# MJU.net
KiCad netlist of a schematic drawn in EAGLE
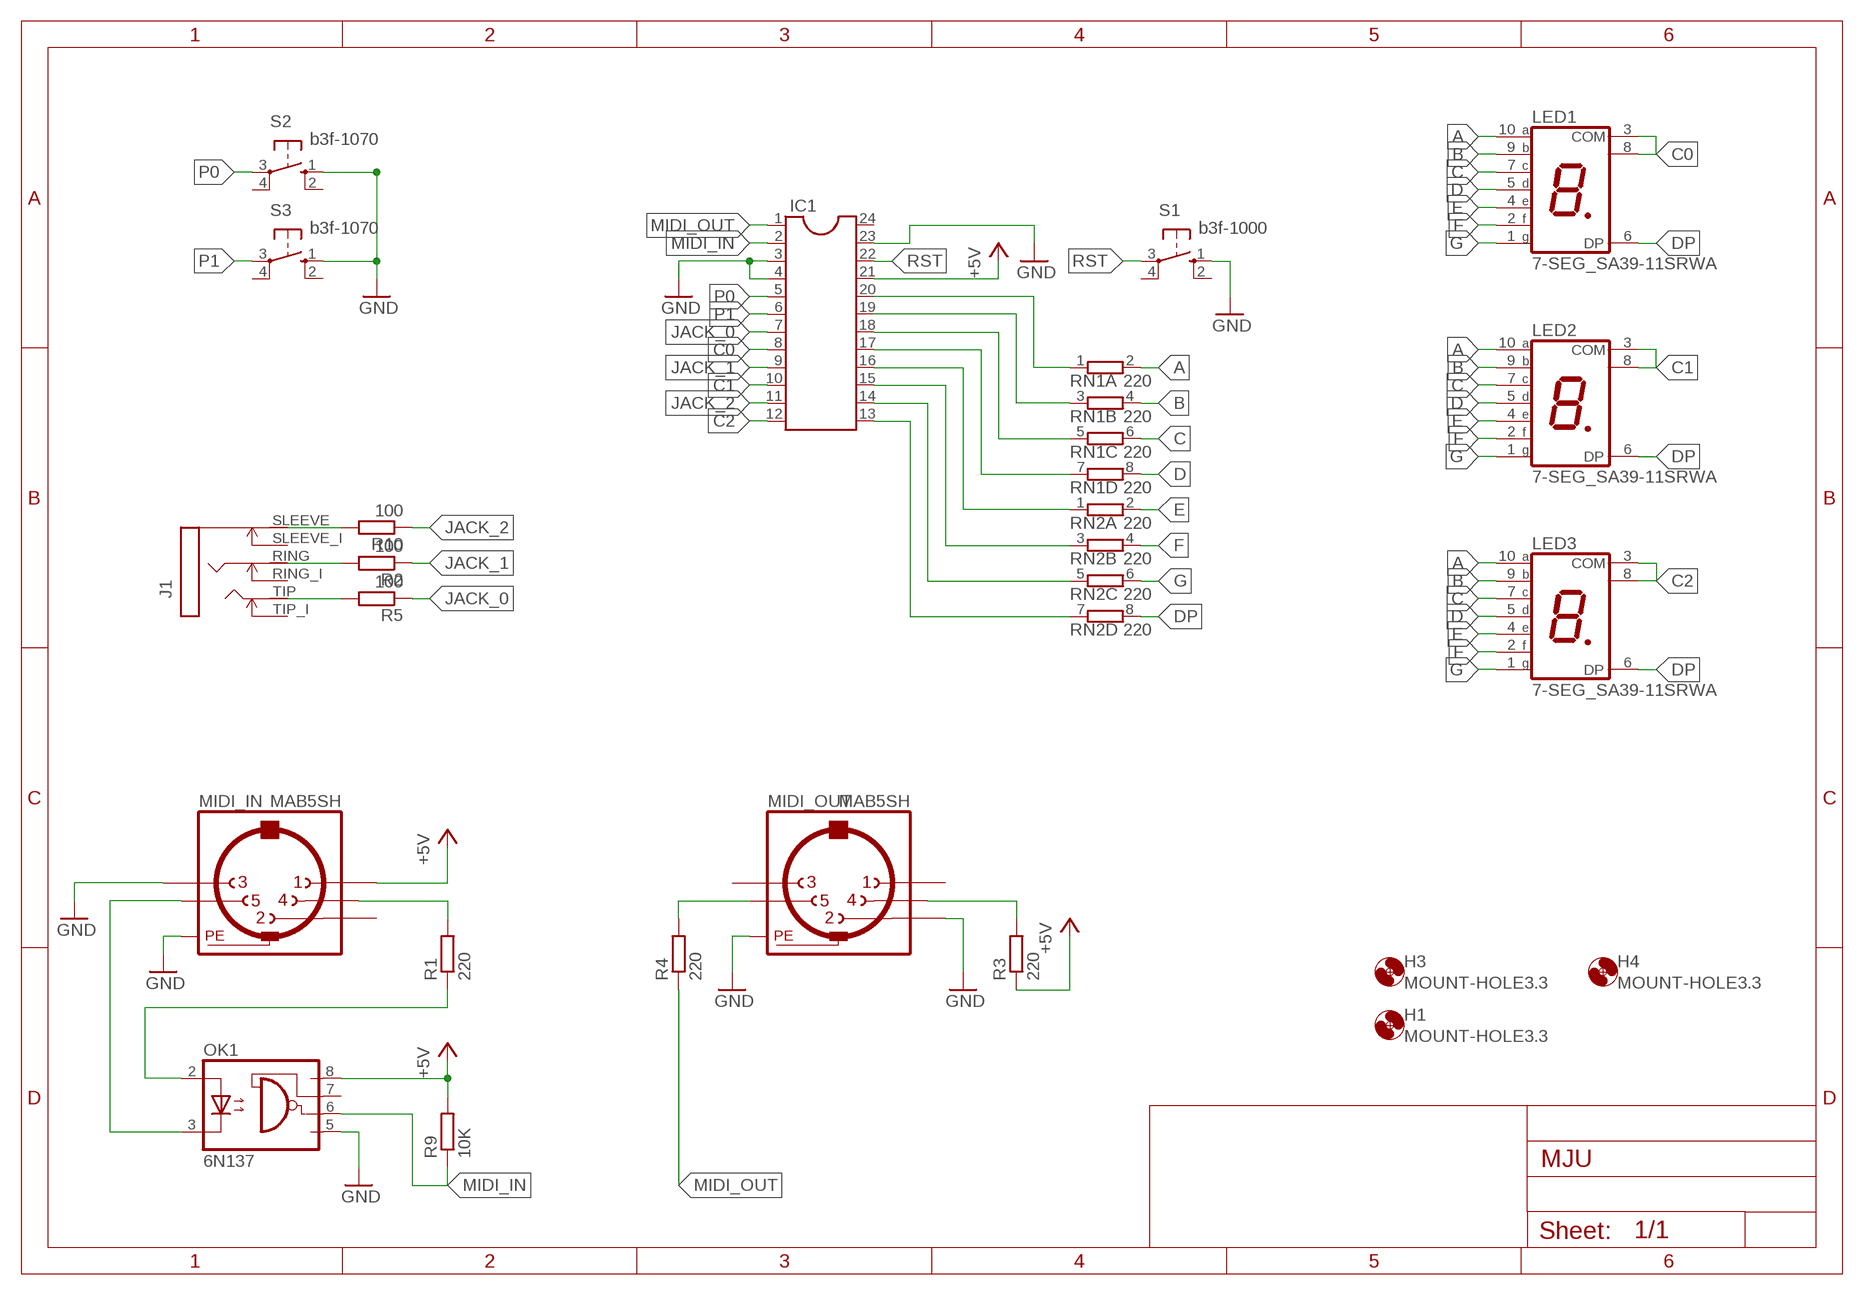
[diagram p0: schematic, sheet 1]

(export (version "E")
  (design (tool "Eeschema 10.0.6"))
  (components
    (comp (ref "H1")
      (value "MOUNT-HOLE3.3")
      (footprint "eagle-import:3,3")
      (libsource (lib "eagle-import") (part "MOUNT-HOLE3.3"))
    )
    (comp (ref "H3")
      (value "MOUNT-HOLE3.3")
      (footprint "eagle-import:3,3")
      (libsource (lib "eagle-import") (part "MOUNT-HOLE3.3"))
    )
    (comp (ref "H4")
      (value "MOUNT-HOLE3.3")
      (footprint "eagle-import:3,3")
      (libsource (lib "eagle-import") (part "MOUNT-HOLE3.3"))
    )
    (comp (ref "IC1")
      (value "DIL24-6")
      (footprint "eagle-import:DIL24-6")
      (libsource (lib "eagle-import") (part "DIL24-6"))
    )
    (comp (ref "J1")
      (value "STEREOSWJACK_ST_TRS_INT")
      (footprint "eagle-import:ST_JACK_TRS_INT")
      (libsource (lib "eagle-import") (part "STEREOSWJACK_ST_TRS_INT"))
    )
    (comp (ref "LED1")
      (value "7-SEG_SA39-11SRWA")
      (footprint "eagle-import:SA39-11SRWA")
      (libsource (lib "eagle-import") (part "7-SEG_SA39-11SRWA"))
    )
    (comp (ref "LED2")
      (value "7-SEG_SA39-11SRWA")
      (footprint "eagle-import:SA39-11SRWA")
      (libsource (lib "eagle-import") (part "7-SEG_SA39-11SRWA"))
    )
    (comp (ref "LED3")
      (value "7-SEG_SA39-11SRWA")
      (footprint "eagle-import:SA39-11SRWA")
      (libsource (lib "eagle-import") (part "7-SEG_SA39-11SRWA"))
    )
    (comp (ref "MIDI_IN")
      (value "MAB5SH")
      (footprint "eagle-import:MAB5SH")
      (libsource (lib "eagle-import") (part "MAB5SH"))
    )
    (comp (ref "MIDI_OUT")
      (value "MAB5SH")
      (footprint "eagle-import:MAB5SH")
      (libsource (lib "eagle-import") (part "MAB5SH"))
    )
    (comp (ref "OK1")
      (value "6N137")
      (footprint "eagle-import:DIL08")
      (libsource (lib "eagle-import") (part "6N137"))
    )
    (comp (ref "R1")
      (value "220")
      (footprint "eagle-import:0207_7")
      (libsource (lib "eagle-import") (part "R-EU_0207/7"))
    )
    (comp (ref "R2")
      (value "100")
      (footprint "eagle-import:0207_7")
      (libsource (lib "eagle-import") (part "R-EU_0207/7"))
    )
    (comp (ref "R3")
      (value "220")
      (footprint "eagle-import:0207_7")
      (libsource (lib "eagle-import") (part "R-EU_0207/7"))
    )
    (comp (ref "R4")
      (value "220")
      (footprint "eagle-import:0207_7")
      (libsource (lib "eagle-import") (part "R-EU_0207/7"))
    )
    (comp (ref "R5")
      (value "100")
      (footprint "eagle-import:0207_7")
      (libsource (lib "eagle-import") (part "R-EU_0207/7"))
    )
    (comp (ref "R9")
      (value "10K")
      (footprint "eagle-import:0207_7")
      (libsource (lib "eagle-import") (part "R-EU_0207/7"))
    )
    (comp (ref "R10")
      (value "100")
      (footprint "eagle-import:0207_7")
      (libsource (lib "eagle-import") (part "R-EU_0207/7"))
    )
    (comp (ref "RN1")
      (value "220")
      (footprint "eagle-import:SIL8")
      (libsource (lib "eagle-import") (part "E4R"))
    )
    (comp (ref "RN2")
      (value "220")
      (footprint "eagle-import:SIL8")
      (libsource (lib "eagle-import") (part "E4R"))
    )
    (comp (ref "S1")
      (value "b3f-1000")
      (footprint "eagle-import:B3F-10XX")
      (fields (field (name "MPN") "B3F-1000"))
      (libsource (lib "eagle-import") (part "10-XX"))
    )
    (comp (ref "S2")
      (value "b3f-1070")
      (footprint "eagle-import:B3F-10XX")
      (fields (field (name "MPN") "B3F-1000"))
      (libsource (lib "eagle-import") (part "10-XX"))
    )
    (comp (ref "S3")
      (value "b3f-1070")
      (footprint "eagle-import:B3F-10XX")
      (fields (field (name "MPN") "B3F-1000"))
      (libsource (lib "eagle-import") (part "10-XX"))
    )
  )
  (nets
    (net (code "1") (name "+5V") (class "Default")
      (node (ref "IC1") (pin "21") (pinfunction "21_21") (pintype "passive"))
      (node (ref "MIDI_IN") (pin "1") (pinfunction "1_1") (pintype "passive"))
      (node (ref "OK1") (pin "8") (pinfunction "VCC_8") (pintype "passive"))
      (node (ref "R3") (pin "1") (pinfunction "1_1") (pintype "passive"))
      (node (ref "R9") (pin "2") (pinfunction "2_2") (pintype "passive"))
    )
    (net (code "2") (name "A") (class "Default")
      (node (ref "LED1") (pin "10") (pinfunction "A_10") (pintype "passive"))
      (node (ref "LED2") (pin "10") (pinfunction "A_10") (pintype "passive"))
      (node (ref "LED3") (pin "10") (pinfunction "A_10") (pintype "passive"))
      (node (ref "RN1") (pin "2") (pinfunction "2_2") (pintype "passive"))
    )
    (net (code "3") (name "B") (class "Default")
      (node (ref "LED1") (pin "9") (pinfunction "B_9") (pintype "passive"))
      (node (ref "LED2") (pin "9") (pinfunction "B_9") (pintype "passive"))
      (node (ref "LED3") (pin "9") (pinfunction "B_9") (pintype "passive"))
      (node (ref "RN1") (pin "4") (pinfunction "2_4") (pintype "passive"))
    )
    (net (code "4") (name "C") (class "Default")
      (node (ref "LED1") (pin "7") (pinfunction "C_7") (pintype "passive"))
      (node (ref "LED2") (pin "7") (pinfunction "C_7") (pintype "passive"))
      (node (ref "LED3") (pin "7") (pinfunction "C_7") (pintype "passive"))
      (node (ref "RN1") (pin "6") (pinfunction "2_6") (pintype "passive"))
    )
    (net (code "5") (name "C0") (class "Default")
      (node (ref "IC1") (pin "8") (pinfunction "8_8") (pintype "passive"))
      (node (ref "LED1") (pin "3") (pinfunction "COM_3") (pintype "passive"))
      (node (ref "LED1") (pin "8") (pinfunction "COM_8") (pintype "passive"))
    )
    (net (code "6") (name "C1") (class "Default")
      (node (ref "IC1") (pin "10") (pinfunction "10_10") (pintype "passive"))
      (node (ref "LED2") (pin "3") (pinfunction "COM_3") (pintype "passive"))
      (node (ref "LED2") (pin "8") (pinfunction "COM_8") (pintype "passive"))
    )
    (net (code "7") (name "C2") (class "Default")
      (node (ref "IC1") (pin "12") (pinfunction "12_12") (pintype "passive"))
      (node (ref "LED3") (pin "3") (pinfunction "COM_3") (pintype "passive"))
      (node (ref "LED3") (pin "8") (pinfunction "COM_8") (pintype "passive"))
    )
    (net (code "8") (name "D") (class "Default")
      (node (ref "LED1") (pin "5") (pinfunction "D_5") (pintype "passive"))
      (node (ref "LED2") (pin "5") (pinfunction "D_5") (pintype "passive"))
      (node (ref "LED3") (pin "5") (pinfunction "D_5") (pintype "passive"))
      (node (ref "RN1") (pin "8") (pinfunction "2_8") (pintype "passive"))
    )
    (net (code "9") (name "DP") (class "Default")
      (node (ref "LED1") (pin "6") (pinfunction "DP_6") (pintype "passive"))
      (node (ref "LED2") (pin "6") (pinfunction "DP_6") (pintype "passive"))
      (node (ref "LED3") (pin "6") (pinfunction "DP_6") (pintype "passive"))
      (node (ref "RN2") (pin "8") (pinfunction "2_8") (pintype "passive"))
    )
    (net (code "10") (name "E") (class "Default")
      (node (ref "LED1") (pin "4") (pinfunction "E_4") (pintype "passive"))
      (node (ref "LED2") (pin "4") (pinfunction "E_4") (pintype "passive"))
      (node (ref "LED3") (pin "4") (pinfunction "E_4") (pintype "passive"))
      (node (ref "RN2") (pin "2") (pinfunction "2_2") (pintype "passive"))
    )
    (net (code "11") (name "F") (class "Default")
      (node (ref "LED1") (pin "2") (pinfunction "F_2") (pintype "passive"))
      (node (ref "LED2") (pin "2") (pinfunction "F_2") (pintype "passive"))
      (node (ref "LED3") (pin "2") (pinfunction "F_2") (pintype "passive"))
      (node (ref "RN2") (pin "4") (pinfunction "2_4") (pintype "passive"))
    )
    (net (code "12") (name "G") (class "Default")
      (node (ref "LED1") (pin "1") (pinfunction "G_1") (pintype "passive"))
      (node (ref "LED2") (pin "1") (pinfunction "G_1") (pintype "passive"))
      (node (ref "LED3") (pin "1") (pinfunction "G_1") (pintype "passive"))
      (node (ref "RN2") (pin "6") (pinfunction "2_6") (pintype "passive"))
    )
    (net (code "13") (name "GND") (class "Default")
      (node (ref "IC1") (pin "23") (pinfunction "23_23") (pintype "passive"))
      (node (ref "IC1") (pin "3") (pinfunction "3_3") (pintype "passive"))
      (node (ref "IC1") (pin "4") (pinfunction "4_4") (pintype "passive"))
      (node (ref "MIDI_IN") (pin "3") (pinfunction "3_3") (pintype "passive"))
      (node (ref "MIDI_IN") (pin "PE") (pinfunction "PE_PE") (pintype "power_in"))
      (node (ref "MIDI_IN") (pin "PE@") (pinfunction "PE_PE@") (pintype "power_in"))
      (node (ref "MIDI_OUT") (pin "2") (pinfunction "2_2") (pintype "passive"))
      (node (ref "MIDI_OUT") (pin "PE") (pinfunction "PE_PE") (pintype "power_in"))
      (node (ref "MIDI_OUT") (pin "PE@") (pinfunction "PE_PE@") (pintype "power_in"))
      (node (ref "OK1") (pin "5") (pinfunction "GND_5") (pintype "passive"))
      (node (ref "S1") (pin "1") (pinfunction "S_1") (pintype "passive"))
      (node (ref "S2") (pin "1") (pinfunction "S_1") (pintype "passive"))
      (node (ref "S3") (pin "1") (pinfunction "S_1") (pintype "passive"))
    )
    (net (code "14") (name "JACK_0") (class "Default")
      (node (ref "IC1") (pin "7") (pinfunction "7_7") (pintype "passive"))
      (node (ref "R5") (pin "1") (pinfunction "1_1") (pintype "passive"))
    )
    (net (code "15") (name "JACK_1") (class "Default")
      (node (ref "IC1") (pin "9") (pinfunction "9_9") (pintype "passive"))
      (node (ref "R2") (pin "1") (pinfunction "1_1") (pintype "passive"))
    )
    (net (code "16") (name "JACK_2") (class "Default")
      (node (ref "IC1") (pin "11") (pinfunction "11_11") (pintype "passive"))
      (node (ref "R10") (pin "1") (pinfunction "1_1") (pintype "passive"))
    )
    (net (code "17") (name "MIDI_IN") (class "Default")
      (node (ref "IC1") (pin "2") (pinfunction "2_2") (pintype "passive"))
      (node (ref "OK1") (pin "6") (pinfunction "VO_6") (pintype "passive"))
      (node (ref "R9") (pin "1") (pinfunction "1_1") (pintype "passive"))
    )
    (net (code "18") (name "MIDI_OUT") (class "Default")
      (node (ref "IC1") (pin "1") (pinfunction "1_1") (pintype "passive"))
      (node (ref "R4") (pin "1") (pinfunction "1_1") (pintype "passive"))
    )
    (net (code "19") (name "Net-(IC1-Pad16)") (class "Default")
      (node (ref "IC1") (pin "16") (pinfunction "16_16") (pintype "passive"))
      (node (ref "RN2") (pin "1") (pinfunction "1_1") (pintype "passive"))
    )
    (net (code "20") (name "Net-(IC1-Pad20)") (class "Default")
      (node (ref "IC1") (pin "20") (pinfunction "20_20") (pintype "passive"))
      (node (ref "RN1") (pin "1") (pinfunction "1_1") (pintype "passive"))
    )
    (net (code "21") (name "Net-(J1-R)") (class "Default")
      (node (ref "J1") (pin "RING") (pinfunction "R_RING") (pintype "passive"))
      (node (ref "R2") (pin "2") (pinfunction "2_2") (pintype "passive"))
    )
    (net (code "22") (name "Net-(J1-S)") (class "Default")
      (node (ref "J1") (pin "SLEEVE") (pinfunction "S_SLEEVE") (pintype "passive"))
      (node (ref "R10") (pin "2") (pinfunction "2_2") (pintype "passive"))
    )
    (net (code "23") (name "Net-(J1-T)") (class "Default")
      (node (ref "J1") (pin "TIP") (pinfunction "T_TIP") (pintype "passive"))
      (node (ref "R5") (pin "2") (pinfunction "2_2") (pintype "passive"))
    )
    (net (code "24") (name "Net-(MIDI_IN-Pad4)") (class "Default")
      (node (ref "MIDI_IN") (pin "4") (pinfunction "4_4") (pintype "passive"))
      (node (ref "R1") (pin "2") (pinfunction "2_2") (pintype "passive"))
    )
    (net (code "25") (name "Net-(MIDI_OUT-Pad4)") (class "Default")
      (node (ref "MIDI_OUT") (pin "4") (pinfunction "4_4") (pintype "passive"))
      (node (ref "R3") (pin "2") (pinfunction "2_2") (pintype "passive"))
    )
    (net (code "26") (name "Net-(MIDI_OUT-Pad5)") (class "Default")
      (node (ref "MIDI_OUT") (pin "5") (pinfunction "5_5") (pintype "passive"))
      (node (ref "R4") (pin "2") (pinfunction "2_2") (pintype "passive"))
    )
    (net (code "27") (name "Net-(OK1-A)") (class "Default")
      (node (ref "OK1") (pin "2") (pinfunction "A_2") (pintype "passive"))
      (node (ref "R1") (pin "1") (pinfunction "1_1") (pintype "passive"))
    )
    (net (code "28") (name "Net-(OK1-C)") (class "Default")
      (node (ref "MIDI_IN") (pin "5") (pinfunction "5_5") (pintype "passive"))
      (node (ref "OK1") (pin "3") (pinfunction "C_3") (pintype "passive"))
    )
    (net (code "29") (name "Net-(RN1B-1)") (class "Default")
      (node (ref "IC1") (pin "19") (pinfunction "19_19") (pintype "passive"))
      (node (ref "RN1") (pin "3") (pinfunction "1_3") (pintype "passive"))
    )
    (net (code "30") (name "Net-(RN1C-1)") (class "Default")
      (node (ref "IC1") (pin "18") (pinfunction "18_18") (pintype "passive"))
      (node (ref "RN1") (pin "5") (pinfunction "1_5") (pintype "passive"))
    )
    (net (code "31") (name "Net-(RN1D-1)") (class "Default")
      (node (ref "IC1") (pin "17") (pinfunction "17_17") (pintype "passive"))
      (node (ref "RN1") (pin "7") (pinfunction "1_7") (pintype "passive"))
    )
    (net (code "32") (name "Net-(RN2B-1)") (class "Default")
      (node (ref "IC1") (pin "15") (pinfunction "15_15") (pintype "passive"))
      (node (ref "RN2") (pin "3") (pinfunction "1_3") (pintype "passive"))
    )
    (net (code "33") (name "Net-(RN2C-1)") (class "Default")
      (node (ref "IC1") (pin "14") (pinfunction "14_14") (pintype "passive"))
      (node (ref "RN2") (pin "5") (pinfunction "1_5") (pintype "passive"))
    )
    (net (code "34") (name "Net-(RN2D-1)") (class "Default")
      (node (ref "IC1") (pin "13") (pinfunction "13_13") (pintype "passive"))
      (node (ref "RN2") (pin "7") (pinfunction "1_7") (pintype "passive"))
    )
    (net (code "35") (name "P0") (class "Default")
      (node (ref "IC1") (pin "5") (pinfunction "5_5") (pintype "passive"))
      (node (ref "S2") (pin "3") (pinfunction "P_3") (pintype "passive"))
    )
    (net (code "36") (name "P1") (class "Default")
      (node (ref "IC1") (pin "6") (pinfunction "6_6") (pintype "passive"))
      (node (ref "S3") (pin "3") (pinfunction "P_3") (pintype "passive"))
    )
    (net (code "37") (name "RST") (class "Default")
      (node (ref "IC1") (pin "22") (pinfunction "22_22") (pintype "passive"))
      (node (ref "S1") (pin "3") (pinfunction "P_3") (pintype "passive"))
    )
    (net (code "38") (name "unconnected-(IC1-Pad24)") (class "Default")
      (node (ref "IC1") (pin "24") (pinfunction "24_24") (pintype "passive"))
    )
    (net (code "39") (name "unconnected-(J1-RN-PadRING_I)") (class "Default")
      (node (ref "J1") (pin "RING_I") (pinfunction "RN_RING_I") (pintype "passive"))
    )
    (net (code "40") (name "unconnected-(J1-SN-PadSLEEVE_I)") (class "Default")
      (node (ref "J1") (pin "SLEEVE_I") (pinfunction "SN_SLEEVE_I") (pintype "passive"))
    )
    (net (code "41") (name "unconnected-(J1-TN-PadTIP_I)") (class "Default")
      (node (ref "J1") (pin "TIP_I") (pinfunction "TN_TIP_I") (pintype "passive"))
    )
    (net (code "42") (name "unconnected-(MIDI_IN-Pad2)") (class "Default")
      (node (ref "MIDI_IN") (pin "2") (pinfunction "2_2") (pintype "passive"))
    )
    (net (code "43") (name "unconnected-(MIDI_OUT-Pad1)") (class "Default")
      (node (ref "MIDI_OUT") (pin "1") (pinfunction "1_1") (pintype "passive"))
    )
    (net (code "44") (name "unconnected-(MIDI_OUT-Pad3)") (class "Default")
      (node (ref "MIDI_OUT") (pin "3") (pinfunction "3_3") (pintype "passive"))
    )
    (net (code "45") (name "unconnected-(OK1-VE-Pad7)") (class "Default")
      (node (ref "OK1") (pin "7") (pinfunction "VE_7") (pintype "passive"))
    )
    (net (code "46") (name "unconnected-(S1-P1-Pad4)") (class "Default")
      (node (ref "S1") (pin "4") (pinfunction "P1_4") (pintype "passive"))
    )
    (net (code "47") (name "unconnected-(S1-S1-Pad2)") (class "Default")
      (node (ref "S1") (pin "2") (pinfunction "S1_2") (pintype "passive"))
    )
    (net (code "48") (name "unconnected-(S2-P1-Pad4)") (class "Default")
      (node (ref "S2") (pin "4") (pinfunction "P1_4") (pintype "passive"))
    )
    (net (code "49") (name "unconnected-(S2-S1-Pad2)") (class "Default")
      (node (ref "S2") (pin "2") (pinfunction "S1_2") (pintype "passive"))
    )
    (net (code "50") (name "unconnected-(S3-P1-Pad4)") (class "Default")
      (node (ref "S3") (pin "4") (pinfunction "P1_4") (pintype "passive"))
    )
    (net (code "51") (name "unconnected-(S3-S1-Pad2)") (class "Default")
      (node (ref "S3") (pin "2") (pinfunction "S1_2") (pintype "passive"))
    )
  )
)
